# 7draft_onBoard.net
KiCad netlist of a schematic drawn in EAGLE
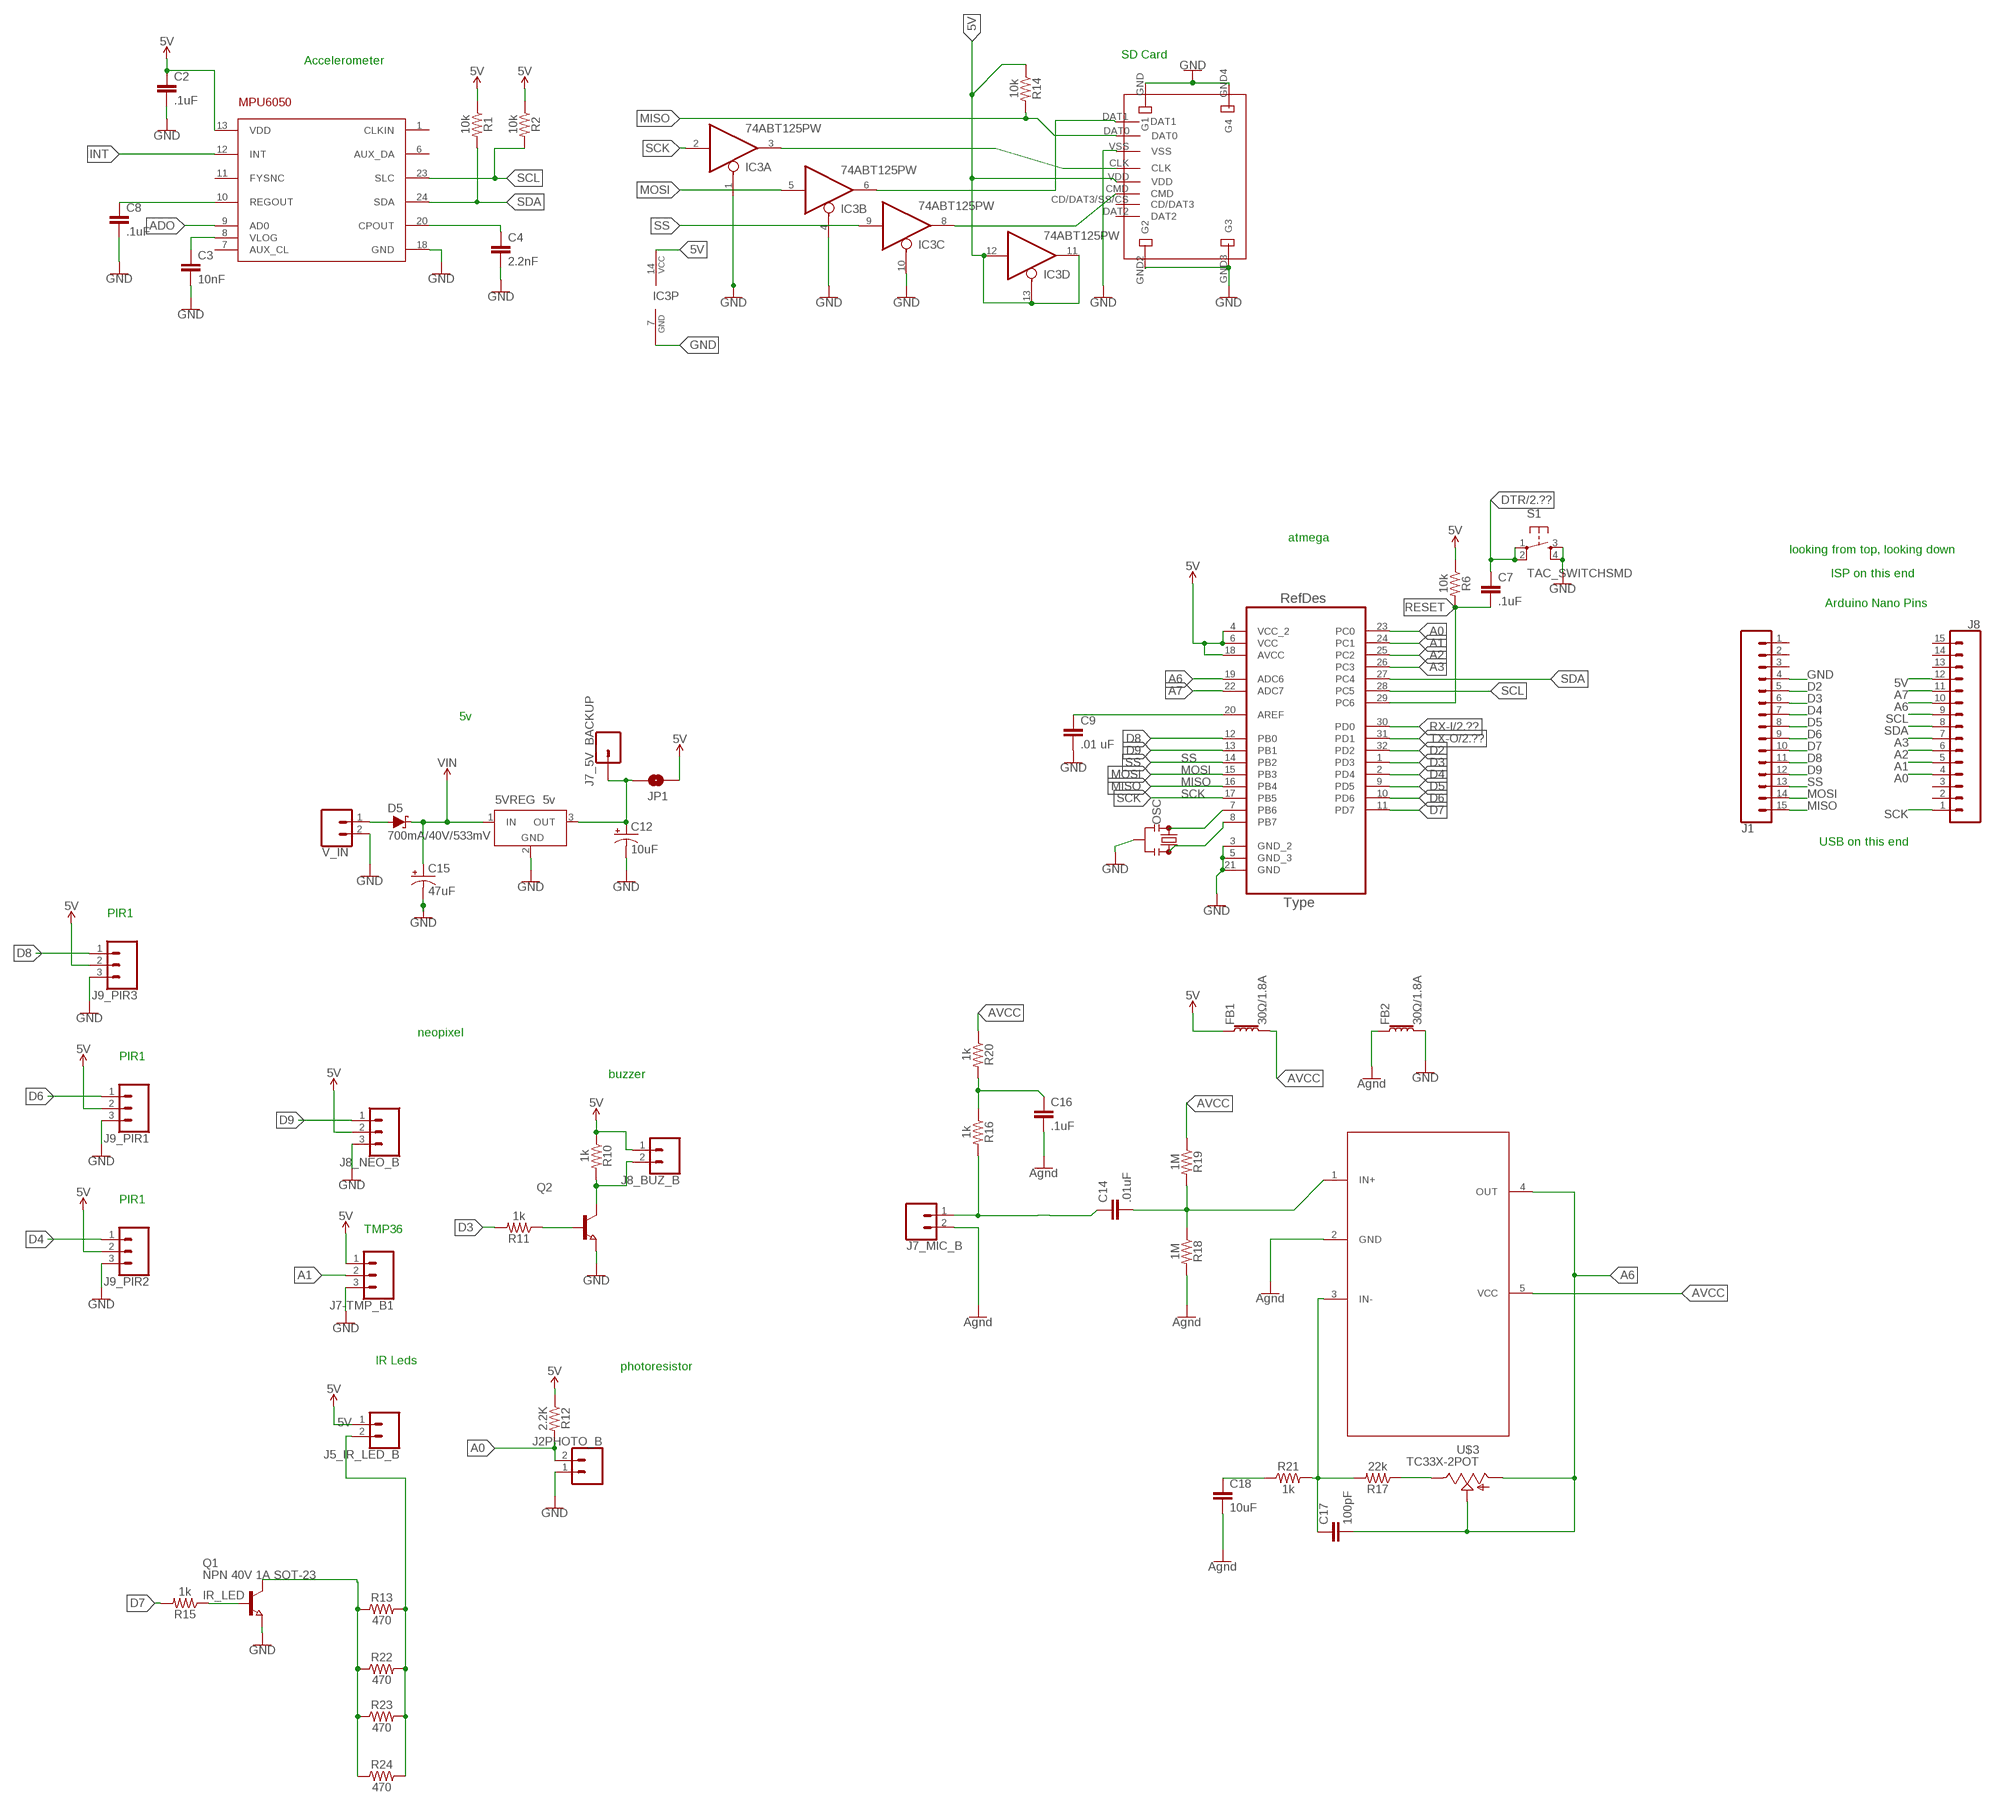
[diagram p0: schematic, sheet 1]
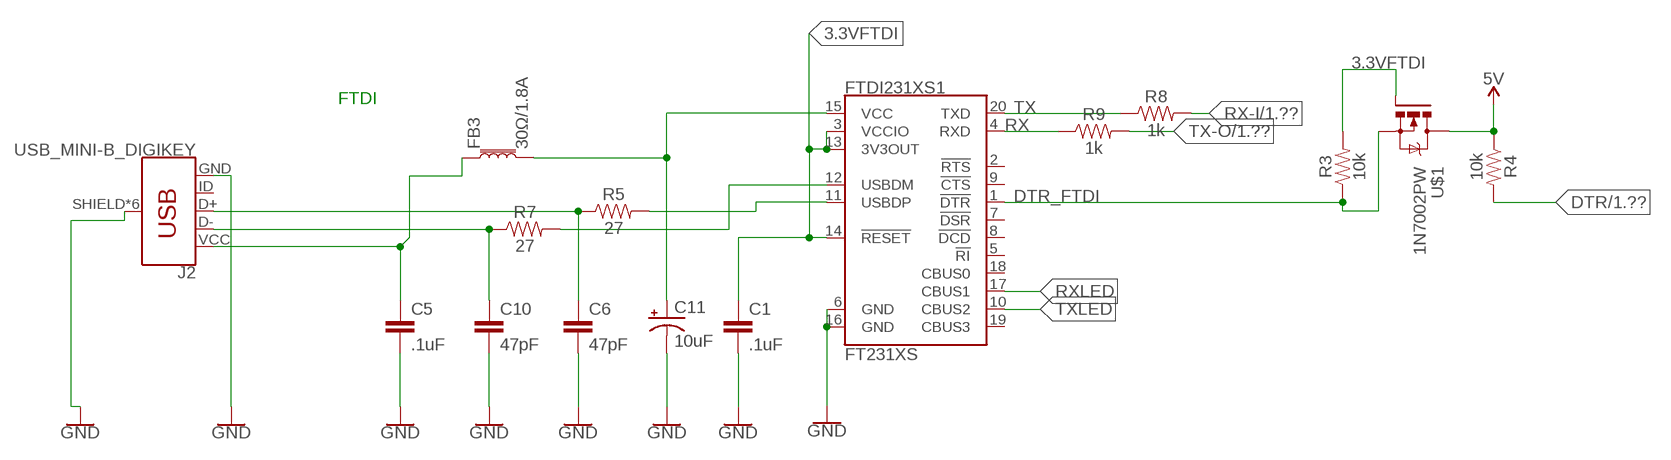
[diagram p1: schematic, sheet 2]

(export (version "E")
  (design (tool "Eeschema 10.0.6"))
  (components
    (comp (ref "C1")
      (value ".1uF")
      (footprint "eagle-import:0402-CAP")
      (libsource (lib "eagle-import") (part ".22UF-CER"))
    )
    (comp (ref "C5")
      (value ".1uF")
      (footprint "eagle-import:0402-CAP")
      (libsource (lib "eagle-import") (part ".22UF-CER"))
    )
    (comp (ref "C6")
      (value "47pF")
      (footprint "eagle-import:0402-CAP")
      (libsource (lib "eagle-import") (part ".22UF-CER"))
    )
    (comp (ref "C10")
      (value "47pF")
      (footprint "eagle-import:0402-CAP")
      (libsource (lib "eagle-import") (part ".22UF-CER"))
    )
    (comp (ref "C11")
      (value "10uF")
      (footprint "eagle-import:EIA3216")
      (libsource (lib "eagle-import") (part "10UF-TANT"))
    )
    (comp (ref "FB3")
      (value "30Ω/1.8A")
      (footprint "eagle-import:0603")
      (libsource (lib "eagle-import") (part "FERRITE_BEAD-0603"))
    )
    (comp (ref "FTDI231XS1")
      (value "FT231XS")
      (footprint "eagle-import:SSOP20_L")
      (libsource (lib "eagle-import") (part "FT231XS"))
    )
    (comp (ref "J2")
      (value "USB_MINI-B_DIGIKEY")
      (footprint "eagle-import:MICRO-USB-DIGIKEY-FCI2")
      (libsource (lib "eagle-import") (part "USB_MINI-B_DIGIKEY"))
    )
    (comp (ref "R3")
      (value "10k")
      (footprint "eagle-import:0603")
      (libsource (lib "eagle-import") (part "0.05OHM-0603-1/5W-1%"))
    )
    (comp (ref "R4")
      (value "10k")
      (footprint "eagle-import:0603")
      (libsource (lib "eagle-import") (part "0.05OHM-0603-1/5W-1%"))
    )
    (comp (ref "R5")
      (value "27")
      (footprint "eagle-import:0603")
      (libsource (lib "eagle-import") (part "0.05OHM-0603-1/5W-1%"))
    )
    (comp (ref "R7")
      (value "27")
      (footprint "eagle-import:0603")
      (libsource (lib "eagle-import") (part "0.05OHM-0603-1/5W-1%"))
    )
    (comp (ref "R8")
      (value "1k")
      (footprint "eagle-import:0603")
      (libsource (lib "eagle-import") (part "0.05OHM-0603-1/5W-1%"))
    )
    (comp (ref "R9")
      (value "1k")
      (footprint "eagle-import:0603")
      (libsource (lib "eagle-import") (part "0.05OHM-0603-1/5W-1%"))
    )
    (comp (ref "U$1")
      (value "1N7002PW")
      (footprint "eagle-import:SOT323W_INFINEON")
      (libsource (lib "eagle-import") (part "1N7002PW"))
    )
    (comp (ref "5VREG")
      (value "5v")
      (footprint "eagle-import:SOT223")
      (fields (field (name "MPN") "LT1129CST-5#PBF"))
      (libsource (lib "eagle-import") (part "LT1129CST5"))
    )
    (comp (ref "ATMEGA328P-AU")
      (value "ATMEGA328P-AU")
      (footprint "eagle-import:QFP80P900X900X120-32N")
      (libsource (lib "eagle-import") (part "ATMEGA328P-AU"))
    )
    (comp (ref "C2")
      (value ".1uF")
      (footprint "eagle-import:0402-CAP")
      (libsource (lib "eagle-import") (part ".22UF-CER"))
    )
    (comp (ref "C3")
      (value "10nF")
      (footprint "eagle-import:0402-CAP")
      (libsource (lib "eagle-import") (part ".22UF-CER"))
    )
    (comp (ref "C4")
      (value "2.2nF")
      (footprint "eagle-import:0402-CAP")
      (libsource (lib "eagle-import") (part ".22UF-CER"))
    )
    (comp (ref "C7")
      (value ".1uF")
      (footprint "eagle-import:0402-CAP")
      (libsource (lib "eagle-import") (part ".22UF-CER"))
    )
    (comp (ref "C8")
      (value ".1uF")
      (footprint "eagle-import:0402-CAP")
      (libsource (lib "eagle-import") (part ".22UF-CER"))
    )
    (comp (ref "C9")
      (value ".01 uF")
      (footprint "eagle-import:0402-CAP")
      (libsource (lib "eagle-import") (part ".22UF-CER"))
    )
    (comp (ref "C12")
      (value "10uF")
      (footprint "eagle-import:EIA3216")
      (libsource (lib "eagle-import") (part "10UF-TANT"))
    )
    (comp (ref "C14")
      (value ".01uF")
      (footprint "eagle-import:0402-CAP")
      (libsource (lib "eagle-import") (part ".22UF-CER"))
    )
    (comp (ref "C15")
      (value "47uF")
      (footprint "eagle-import:EIA3216")
      (libsource (lib "eagle-import") (part "10UF-TANT"))
    )
    (comp (ref "C16")
      (value ".1uF")
      (footprint "eagle-import:0402-CAP")
      (libsource (lib "eagle-import") (part ".22UF-CER"))
    )
    (comp (ref "C17")
      (value "100pF")
      (footprint "eagle-import:0402-CAP")
      (libsource (lib "eagle-import") (part ".22UF-CER"))
    )
    (comp (ref "C18")
      (value "10uF")
      (footprint "eagle-import:0402-CAP")
      (libsource (lib "eagle-import") (part ".22UF-CER"))
    )
    (comp (ref "D5")
      (value "700mA/40V/533mV")
      (footprint "eagle-import:SOT23-3")
      (libsource (lib "eagle-import") (part "DIODE-SCHOTTKY-ZLLS500"))
    )
    (comp (ref "FB1")
      (value "30Ω/1.8A")
      (footprint "eagle-import:0603")
      (libsource (lib "eagle-import") (part "FERRITE_BEAD-0603"))
    )
    (comp (ref "FB2")
      (value "30Ω/1.8A")
      (footprint "eagle-import:0603")
      (libsource (lib "eagle-import") (part "FERRITE_BEAD-0603"))
    )
    (comp (ref "IC3")
      (value "74ABT125PW")
      (footprint "eagle-import:TSSOP14")
      (libsource (lib "eagle-import") (part "74125PWABT"))
    )
    (comp (ref "IC4")
      (value "MAX4466KS")
      (footprint "eagle-import:SC70-5")
      (libsource (lib "eagle-import") (part "MAX4466KS"))
    )
    (comp (ref "J1")
      (value "CONN_15")
      (footprint "eagle-import:1X15")
      (libsource (lib "eagle-import") (part "CONN_15"))
    )
    (comp (ref "J2PHOTO_B")
      (value "CONN_02LOCK")
      (footprint "eagle-import:1X02_LOCK")
      (libsource (lib "eagle-import") (part "CONN_02LOCK"))
    )
    (comp (ref "J5_IR_LED_B")
      (value "CONN_02LOCK")
      (footprint "eagle-import:1X02_LOCK")
      (libsource (lib "eagle-import") (part "CONN_02LOCK"))
    )
    (comp (ref "J7-TMP_B1")
      (value "CONN_03")
      (footprint "eagle-import:1X03")
      (libsource (lib "eagle-import") (part "CONN_03"))
    )
    (comp (ref "J7_5V_BACKUP")
      (value "CONN_01")
      (footprint "eagle-import:1X01")
      (libsource (lib "eagle-import") (part "CONN_01"))
    )
    (comp (ref "J7_MIC_B")
      (value "CONN_02LOCK")
      (footprint "eagle-import:1X02_LOCK")
      (libsource (lib "eagle-import") (part "CONN_02LOCK"))
    )
    (comp (ref "J8")
      (value "CONN_15")
      (footprint "eagle-import:1X15")
      (libsource (lib "eagle-import") (part "CONN_15"))
    )
    (comp (ref "J8_BUZ_B")
      (value "CONN_02LOCK")
      (footprint "eagle-import:1X02_LOCK")
      (libsource (lib "eagle-import") (part "CONN_02LOCK"))
    )
    (comp (ref "J8_NEO_B")
      (value "CONN_03")
      (footprint "eagle-import:1X03")
      (libsource (lib "eagle-import") (part "CONN_03"))
    )
    (comp (ref "J9_PIR1")
      (value "CONN_03")
      (footprint "eagle-import:1X03")
      (libsource (lib "eagle-import") (part "CONN_03"))
    )
    (comp (ref "J9_PIR2")
      (value "CONN_03")
      (footprint "eagle-import:1X03")
      (libsource (lib "eagle-import") (part "CONN_03"))
    )
    (comp (ref "J9_PIR3")
      (value "CONN_03")
      (footprint "eagle-import:1X03")
      (libsource (lib "eagle-import") (part "CONN_03"))
    )
    (comp (ref "JP1")
      (value "JUMPER-SMT_2_NO_NO-SILK_ROUND")
      (footprint "eagle-import:SMT-JUMPER_2_NO_NO-SILK_ROUND")
      (libsource (lib "eagle-import") (part "JUMPER-SMT_2_NO_NO-SILK_ROUND"))
    )
    (comp (ref "MPU6050")
      (value "MPU-6050")
      (footprint "eagle-import:QFN24-4X4")
      (libsource (lib "eagle-import") (part "MPU-6050"))
    )
    (comp (ref "OSC")
      (value "RESONATORSMD-3.2X1.3")
      (footprint "eagle-import:RESONATOR-SMD-3.2X1.3")
      (libsource (lib "eagle-import") (part "RESONATORSMD-3.2X1.3"))
    )
    (comp (ref "Q1")
      (value "NPN 40V 1A SOT-23")
      (footprint "eagle-import:SOT23")
      (libsource (lib "eagle-import") (part "NPN-TRANSISTOR_SOT23"))
    )
    (comp (ref "Q2")
      (value "NPN-TRANSISTOR_SOT23")
      (footprint "eagle-import:SOT23")
      (libsource (lib "eagle-import") (part "NPN-TRANSISTOR_SOT23"))
    )
    (comp (ref "R1")
      (value "10k")
      (footprint "eagle-import:0603")
      (libsource (lib "eagle-import") (part "0.05OHM-0603-1/5W-1%"))
    )
    (comp (ref "R2")
      (value "10k")
      (footprint "eagle-import:0603")
      (libsource (lib "eagle-import") (part "0.05OHM-0603-1/5W-1%"))
    )
    (comp (ref "R6")
      (value "10k")
      (footprint "eagle-import:0603")
      (libsource (lib "eagle-import") (part "0.05OHM-0603-1/5W-1%"))
    )
    (comp (ref "R10")
      (value "1k")
      (footprint "eagle-import:0603")
      (libsource (lib "eagle-import") (part "0.05OHM-0603-1/5W-1%"))
    )
    (comp (ref "R11")
      (value "1k")
      (footprint "eagle-import:0603")
      (libsource (lib "eagle-import") (part "0.05OHM-0603-1/5W-1%"))
    )
    (comp (ref "R12")
      (value "2.2K")
      (footprint "eagle-import:0603")
      (libsource (lib "eagle-import") (part "0.05OHM-0603-1/5W-1%"))
    )
    (comp (ref "R13")
      (value "470")
      (footprint "eagle-import:0603")
      (libsource (lib "eagle-import") (part "2.2MOHM-1/10W-5%(0603)"))
    )
    (comp (ref "R14")
      (value "10k")
      (footprint "eagle-import:0603")
      (libsource (lib "eagle-import") (part "0.05OHM-0603-1/5W-1%"))
    )
    (comp (ref "R15")
      (value "1k")
      (footprint "eagle-import:0603")
      (libsource (lib "eagle-import") (part "0.05OHM-0603-1/5W-1%"))
    )
    (comp (ref "R16")
      (value "1k")
      (footprint "eagle-import:0603")
      (libsource (lib "eagle-import") (part "0.05OHM-0603-1/5W-1%"))
    )
    (comp (ref "R17")
      (value "22k")
      (footprint "eagle-import:0603")
      (libsource (lib "eagle-import") (part "0.05OHM-0603-1/5W-1%"))
    )
    (comp (ref "R18")
      (value "1M")
      (footprint "eagle-import:0603")
      (libsource (lib "eagle-import") (part "0.05OHM-0603-1/5W-1%"))
    )
    (comp (ref "R19")
      (value "1M")
      (footprint "eagle-import:0603")
      (libsource (lib "eagle-import") (part "0.05OHM-0603-1/5W-1%"))
    )
    (comp (ref "R20")
      (value "1k")
      (footprint "eagle-import:0603")
      (libsource (lib "eagle-import") (part "0.05OHM-0603-1/5W-1%"))
    )
    (comp (ref "R21")
      (value "1k")
      (footprint "eagle-import:0603")
      (libsource (lib "eagle-import") (part "0.05OHM-0603-1/5W-1%"))
    )
    (comp (ref "R22")
      (value "470")
      (footprint "eagle-import:0603")
      (libsource (lib "eagle-import") (part "2.2MOHM-1/10W-5%(0603)"))
    )
    (comp (ref "R23")
      (value "470")
      (footprint "eagle-import:0603")
      (libsource (lib "eagle-import") (part "2.2MOHM-1/10W-5%(0603)"))
    )
    (comp (ref "R24")
      (value "470")
      (footprint "eagle-import:0603")
      (libsource (lib "eagle-import") (part "2.2MOHM-1/10W-5%(0603)"))
    )
    (comp (ref "S1")
      (value "TAC_SWITCHSMD")
      (footprint "eagle-import:TACTILE-SWITCH-SMD")
      (libsource (lib "eagle-import") (part "TAC_SWITCHSMD"))
    )
    (comp (ref "U$2")
      (value "WM6698TR-ND_MICROSD")
      (footprint "eagle-import:MICROSD2")
      (libsource (lib "eagle-import") (part "WM6698TR-ND_MICROSD"))
    )
    (comp (ref "U$3")
      (value "TC33X-2POT")
      (footprint "eagle-import:TC33X-2")
      (libsource (lib "eagle-import") (part "TC33X-2POT"))
    )
    (comp (ref "V_IN")
      (value "CONN_02LOCK")
      (footprint "eagle-import:1X02_LOCK")
      (libsource (lib "eagle-import") (part "CONN_02LOCK"))
    )
  )
  (nets
    (net (code "1") (name "3.3VFTDI") (class "Default")
      (node (ref "C1") (pin "1") (pinfunction "1_1") (pintype "passive"))
      (node (ref "FTDI231XS1") (pin "13") (pinfunction "3V3OUT_13") (pintype "bidirectional"))
      (node (ref "FTDI231XS1") (pin "14") (pinfunction "~{RESET}_14") (pintype "bidirectional"))
      (node (ref "FTDI231XS1") (pin "3") (pinfunction "VCCIO_3") (pintype "bidirectional"))
      (node (ref "R3") (pin "2") (pinfunction "2_2") (pintype "passive"))
      (node (ref "U$1") (pin "1") (pinfunction "G_1") (pintype "passive"))
    )
    (net (code "2") (name "5V") (class "Default")
      (node (ref "ATMEGA328P-AU") (pin "18") (pinfunction "AVCC_18") (pintype "power_in"))
      (node (ref "ATMEGA328P-AU") (pin "4") (pinfunction "VCC_2_4") (pintype "power_in"))
      (node (ref "ATMEGA328P-AU") (pin "6") (pinfunction "VCC_6") (pintype "power_in"))
      (node (ref "C2") (pin "1") (pinfunction "1_1") (pintype "passive"))
      (node (ref "FB1") (pin "1") (pinfunction "1_1") (pintype "passive"))
      (node (ref "IC3") (pin "11") (pinfunction "O_11") (pintype "tri_state"))
      (node (ref "IC3") (pin "12") (pinfunction "I_12") (pintype "input"))
      (node (ref "IC3") (pin "13") (pinfunction "OE_13") (pintype "input"))
      (node (ref "IC3") (pin "14") (pinfunction "VCC_14") (pintype "power_in"))
      (node (ref "J5_IR_LED_B") (pin "1") (pinfunction "1_1") (pintype "passive"))
      (node (ref "J7-TMP_B1") (pin "1") (pinfunction "1_1") (pintype "passive"))
      (node (ref "J8") (pin "12") (pinfunction "12_12") (pintype "passive"))
      (node (ref "J8_BUZ_B") (pin "1") (pinfunction "1_1") (pintype "passive"))
      (node (ref "J8_NEO_B") (pin "2") (pinfunction "2_2") (pintype "passive"))
      (node (ref "J9_PIR1") (pin "2") (pinfunction "2_2") (pintype "passive"))
      (node (ref "J9_PIR2") (pin "2") (pinfunction "2_2") (pintype "passive"))
      (node (ref "J9_PIR3") (pin "2") (pinfunction "2_2") (pintype "passive"))
      (node (ref "JP1") (pin "1") (pinfunction "1_1") (pintype "passive"))
      (node (ref "MPU6050") (pin "13") (pinfunction "VDD_13") (pintype "bidirectional"))
      (node (ref "R1") (pin "1") (pinfunction "1_1") (pintype "passive"))
      (node (ref "R10") (pin "1") (pinfunction "1_1") (pintype "passive"))
      (node (ref "R12") (pin "1") (pinfunction "1_1") (pintype "passive"))
      (node (ref "R14") (pin "1") (pinfunction "1_1") (pintype "passive"))
      (node (ref "R2") (pin "1") (pinfunction "1_1") (pintype "passive"))
      (node (ref "R4") (pin "1") (pinfunction "1_1") (pintype "passive"))
      (node (ref "R6") (pin "1") (pinfunction "1_1") (pintype "passive"))
      (node (ref "U$1") (pin "3") (pinfunction "D_3") (pintype "passive"))
      (node (ref "U$2") (pin "VDD") (pinfunction "VDD_VDD") (pintype "bidirectional"))
    )
    (net (code "3") (name "A0") (class "Default")
      (node (ref "ATMEGA328P-AU") (pin "23") (pinfunction "PC0_23") (pintype "bidirectional"))
      (node (ref "J2PHOTO_B") (pin "2") (pinfunction "2_2") (pintype "passive"))
      (node (ref "J8") (pin "4") (pinfunction "4_4") (pintype "passive"))
      (node (ref "R12") (pin "2") (pinfunction "2_2") (pintype "passive"))
    )
    (net (code "4") (name "A1") (class "Default")
      (node (ref "ATMEGA328P-AU") (pin "24") (pinfunction "PC1_24") (pintype "bidirectional"))
      (node (ref "J7-TMP_B1") (pin "2") (pinfunction "2_2") (pintype "passive"))
      (node (ref "J8") (pin "5") (pinfunction "5_5") (pintype "passive"))
    )
    (net (code "5") (name "A2") (class "Default")
      (node (ref "ATMEGA328P-AU") (pin "25") (pinfunction "PC2_25") (pintype "bidirectional"))
      (node (ref "J8") (pin "6") (pinfunction "6_6") (pintype "passive"))
    )
    (net (code "6") (name "A3") (class "Default")
      (node (ref "ATMEGA328P-AU") (pin "26") (pinfunction "PC3_26") (pintype "bidirectional"))
      (node (ref "J8") (pin "7") (pinfunction "7_7") (pintype "passive"))
    )
    (net (code "7") (name "A6") (class "Default")
      (node (ref "ATMEGA328P-AU") (pin "19") (pinfunction "ADC6_19") (pintype "input"))
      (node (ref "C17") (pin "2") (pinfunction "2_2") (pintype "passive"))
      (node (ref "IC4") (pin "4") (pinfunction "OUT_4") (pintype "bidirectional"))
      (node (ref "J8") (pin "10") (pinfunction "10_10") (pintype "passive"))
      (node (ref "U$3") (pin "2") (pinfunction "2_2") (pintype "passive"))
      (node (ref "U$3") (pin "3") (pinfunction "3_3") (pintype "passive"))
    )
    (net (code "8") (name "A7") (class "Default")
      (node (ref "ATMEGA328P-AU") (pin "22") (pinfunction "ADC7_22") (pintype "input"))
      (node (ref "J8") (pin "11") (pinfunction "11_11") (pintype "passive"))
    )
    (net (code "9") (name "ADO") (class "Default")
      (node (ref "MPU6050") (pin "9") (pinfunction "AD0_9") (pintype "bidirectional"))
    )
    (net (code "10") (name "AVCC") (class "Default")
      (node (ref "FB1") (pin "2") (pinfunction "2_2") (pintype "passive"))
      (node (ref "IC4") (pin "5") (pinfunction "VCC_5") (pintype "bidirectional"))
      (node (ref "R19") (pin "1") (pinfunction "1_1") (pintype "passive"))
      (node (ref "R20") (pin "1") (pinfunction "1_1") (pintype "passive"))
    )
    (net (code "11") (name "D2") (class "Default")
      (node (ref "ATMEGA328P-AU") (pin "32") (pinfunction "PD2_32") (pintype "bidirectional"))
      (node (ref "J1") (pin "5") (pinfunction "5_5") (pintype "passive"))
    )
    (net (code "12") (name "D3") (class "Default")
      (node (ref "ATMEGA328P-AU") (pin "1") (pinfunction "PD3_1") (pintype "bidirectional"))
      (node (ref "J1") (pin "6") (pinfunction "6_6") (pintype "passive"))
      (node (ref "R11") (pin "2") (pinfunction "2_2") (pintype "passive"))
    )
    (net (code "13") (name "D4") (class "Default")
      (node (ref "ATMEGA328P-AU") (pin "2") (pinfunction "PD4_2") (pintype "bidirectional"))
      (node (ref "J1") (pin "7") (pinfunction "7_7") (pintype "passive"))
      (node (ref "J9_PIR2") (pin "1") (pinfunction "1_1") (pintype "passive"))
    )
    (net (code "14") (name "D5") (class "Default")
      (node (ref "ATMEGA328P-AU") (pin "9") (pinfunction "PD5_9") (pintype "bidirectional"))
      (node (ref "J1") (pin "8") (pinfunction "8_8") (pintype "passive"))
    )
    (net (code "15") (name "D6") (class "Default")
      (node (ref "ATMEGA328P-AU") (pin "10") (pinfunction "PD6_10") (pintype "bidirectional"))
      (node (ref "J1") (pin "9") (pinfunction "9_9") (pintype "passive"))
      (node (ref "J9_PIR1") (pin "1") (pinfunction "1_1") (pintype "passive"))
    )
    (net (code "16") (name "D7") (class "Default")
      (node (ref "ATMEGA328P-AU") (pin "11") (pinfunction "PD7_11") (pintype "bidirectional"))
      (node (ref "J1") (pin "10") (pinfunction "10_10") (pintype "passive"))
      (node (ref "R15") (pin "2") (pinfunction "2_2") (pintype "passive"))
    )
    (net (code "17") (name "D8") (class "Default")
      (node (ref "ATMEGA328P-AU") (pin "12") (pinfunction "PB0_12") (pintype "bidirectional"))
      (node (ref "J1") (pin "11") (pinfunction "11_11") (pintype "passive"))
      (node (ref "J9_PIR3") (pin "1") (pinfunction "1_1") (pintype "passive"))
    )
    (net (code "18") (name "D9") (class "Default")
      (node (ref "ATMEGA328P-AU") (pin "13") (pinfunction "PB1_13") (pintype "bidirectional"))
      (node (ref "J1") (pin "12") (pinfunction "12_12") (pintype "passive"))
      (node (ref "J8_NEO_B") (pin "1") (pinfunction "1_1") (pintype "passive"))
    )
    (net (code "19") (name "DTR") (class "Default")
      (node (ref "C7") (pin "1") (pinfunction "1_1") (pintype "passive"))
      (node (ref "R4") (pin "2") (pinfunction "2_2") (pintype "passive"))
      (node (ref "S1") (pin "1") (pinfunction "1_1") (pintype "passive"))
      (node (ref "S1") (pin "2") (pinfunction "2_2") (pintype "passive"))
    )
    (net (code "20") (name "DTR_FTDI") (class "Default")
      (node (ref "FTDI231XS1") (pin "1") (pinfunction "~{DTR}_1") (pintype "bidirectional"))
      (node (ref "R3") (pin "1") (pinfunction "1_1") (pintype "passive"))
      (node (ref "U$1") (pin "2") (pinfunction "S_2") (pintype "passive"))
    )
    (net (code "21") (name "GND") (class "Default")
      (node (ref "5VREG") (pin "2") (pinfunction "GND_2") (pintype "power_in"))
      (node (ref "ATMEGA328P-AU") (pin "21") (pinfunction "GND_21") (pintype "passive"))
      (node (ref "ATMEGA328P-AU") (pin "3") (pinfunction "GND_2_3") (pintype "passive"))
      (node (ref "ATMEGA328P-AU") (pin "5") (pinfunction "GND_3_5") (pintype "passive"))
      (node (ref "C1") (pin "2") (pinfunction "2_2") (pintype "passive"))
      (node (ref "C10") (pin "2") (pinfunction "2_2") (pintype "passive"))
      (node (ref "C11") (pin "C") (pinfunction "-_C") (pintype "passive"))
      (node (ref "C12") (pin "C") (pinfunction "-_C") (pintype "passive"))
      (node (ref "C15") (pin "C") (pinfunction "-_C") (pintype "passive"))
      (node (ref "C16") (pin "2") (pinfunction "2_2") (pintype "passive"))
      (node (ref "C18") (pin "2") (pinfunction "2_2") (pintype "passive"))
      (node (ref "C2") (pin "2") (pinfunction "2_2") (pintype "passive"))
      (node (ref "C3") (pin "2") (pinfunction "2_2") (pintype "passive"))
      (node (ref "C4") (pin "2") (pinfunction "2_2") (pintype "passive"))
      (node (ref "C5") (pin "2") (pinfunction "2_2") (pintype "passive"))
      (node (ref "C6") (pin "2") (pinfunction "2_2") (pintype "passive"))
      (node (ref "C8") (pin "2") (pinfunction "2_2") (pintype "passive"))
      (node (ref "C9") (pin "2") (pinfunction "2_2") (pintype "passive"))
      (node (ref "FB2") (pin "1") (pinfunction "1_1") (pintype "passive"))
      (node (ref "FB2") (pin "2") (pinfunction "2_2") (pintype "passive"))
      (node (ref "FTDI231XS1") (pin "16") (pinfunction "GND_16") (pintype "bidirectional"))
      (node (ref "FTDI231XS1") (pin "6") (pinfunction "GND_6") (pintype "bidirectional"))
      (node (ref "IC3") (pin "1") (pinfunction "OE_1") (pintype "input"))
      (node (ref "IC3") (pin "10") (pinfunction "OE_10") (pintype "input"))
      (node (ref "IC3") (pin "4") (pinfunction "OE_4") (pintype "input"))
      (node (ref "IC3") (pin "7") (pinfunction "GND_7") (pintype "power_in"))
      (node (ref "IC4") (pin "2") (pinfunction "GND_2") (pintype "bidirectional"))
      (node (ref "J1") (pin "4") (pinfunction "4_4") (pintype "passive"))
      (node (ref "J2") (pin "GND") (pinfunction "GND_GND") (pintype "power_in"))
      (node (ref "J2") (pin "SHIELD") (pinfunction "SHIELD_SHIELD") (pintype "bidirectional"))
      (node (ref "J2") (pin "SHIELD1") (pinfunction "SHIELD_SHIELD1") (pintype "bidirectional"))
      (node (ref "J2") (pin "SHIELD2") (pinfunction "SHIELD_SHIELD2") (pintype "bidirectional"))
      (node (ref "J2") (pin "SHIELD3") (pinfunction "SHIELD_SHIELD3") (pintype "bidirectional"))
      (node (ref "J2") (pin "SHIELD4") (pinfunction "SHIELD_SHIELD4") (pintype "bidirectional"))
      (node (ref "J2") (pin "SHIELD5") (pinfunction "SHIELD_SHIELD5") (pintype "bidirectional"))
      (node (ref "J2PHOTO_B") (pin "1") (pinfunction "1_1") (pintype "passive"))
      (node (ref "J7-TMP_B1") (pin "3") (pinfunction "3_3") (pintype "passive"))
      (node (ref "J7_MIC_B") (pin "2") (pinfunction "2_2") (pintype "passive"))
      (node (ref "J8_NEO_B") (pin "3") (pinfunction "3_3") (pintype "passive"))
      (node (ref "J9_PIR1") (pin "3") (pinfunction "3_3") (pintype "passive"))
      (node (ref "J9_PIR2") (pin "3") (pinfunction "3_3") (pintype "passive"))
      (node (ref "J9_PIR3") (pin "3") (pinfunction "3_3") (pintype "passive"))
      (node (ref "MPU6050") (pin "18") (pinfunction "GND_18") (pintype "bidirectional"))
      (node (ref "OSC") (pin "2") (pinfunction "2_2") (pintype "passive"))
      (node (ref "Q1") (pin "2") (pinfunction "E_2") (pintype "passive"))
      (node (ref "Q2") (pin "2") (pinfunction "E_2") (pintype "passive"))
      (node (ref "R18") (pin "2") (pinfunction "2_2") (pintype "passive"))
      (node (ref "S1") (pin "3") (pinfunction "3_3") (pintype "passive"))
      (node (ref "S1") (pin "4") (pinfunction "4_4") (pintype "passive"))
      (node (ref "U$2") (pin "GND") (pinfunction "G1_GND") (pintype "bidirectional"))
      (node (ref "U$2") (pin "GND2") (pinfunction "G2_GND2") (pintype "bidirectional"))
      (node (ref "U$2") (pin "GND3") (pinfunction "G3_GND3") (pintype "bidirectional"))
      (node (ref "U$2") (pin "GND4") (pinfunction "G4_GND4") (pintype "bidirectional"))
      (node (ref "U$2") (pin "VSS") (pinfunction "VSS_VSS") (pintype "bidirectional"))
      (node (ref "V_IN") (pin "2") (pinfunction "2_2") (pintype "passive"))
    )
    (net (code "22") (name "INT") (class "Default")
      (node (ref "MPU6050") (pin "12") (pinfunction "INT_12") (pintype "bidirectional"))
    )
    (net (code "23") (name "IR_LED") (class "Default")
      (node (ref "Q1") (pin "1") (pinfunction "B_1") (pintype "passive"))
      (node (ref "R15") (pin "1") (pinfunction "1_1") (pintype "passive"))
    )
    (net (code "24") (name "MISO") (class "Default")
      (node (ref "ATMEGA328P-AU") (pin "16") (pinfunction "PB4_16") (pintype "bidirectional"))
      (node (ref "J1") (pin "15") (pinfunction "15_15") (pintype "passive"))
      (node (ref "R14") (pin "2") (pinfunction "2_2") (pintype "passive"))
      (node (ref "U$2") (pin "DAT0") (pinfunction "DAT0_DAT0") (pintype "bidirectional"))
    )
    (net (code "25") (name "MOSI") (class "Default")
      (node (ref "ATMEGA328P-AU") (pin "15") (pinfunction "PB3_15") (pintype "bidirectional"))
      (node (ref "IC3") (pin "5") (pinfunction "I_5") (pintype "input"))
      (node (ref "J1") (pin "14") (pinfunction "14_14") (pintype "passive"))
    )
    (net (code "26") (name "Net-(5VREGA-OUT)") (class "Default")
      (node (ref "5VREG") (pin "3") (pinfunction "OUT_3") (pintype "output"))
      (node (ref "C12") (pin "A") (pinfunction "+_A") (pintype "passive"))
      (node (ref "J7_5V_BACKUP") (pin "1") (pinfunction "1_1") (pintype "passive"))
      (node (ref "JP1") (pin "2") (pinfunction "2_2") (pintype "passive"))
    )
    (net (code "27") (name "Net-(ATMEGA328P-AU-AREF)") (class "Default")
      (node (ref "ATMEGA328P-AU") (pin "20") (pinfunction "AREF_20") (pintype "input"))
      (node (ref "C9") (pin "1") (pinfunction "1_1") (pintype "passive"))
    )
    (net (code "28") (name "Net-(ATMEGA328P-AU-PB6)") (class "Default")
      (node (ref "ATMEGA328P-AU") (pin "7") (pinfunction "PB6_7") (pintype "bidirectional"))
      (node (ref "OSC") (pin "1") (pinfunction "1_1") (pintype "passive"))
    )
    (net (code "29") (name "Net-(ATMEGA328P-AU-PB7)") (class "Default")
      (node (ref "ATMEGA328P-AU") (pin "8") (pinfunction "PB7_8") (pintype "bidirectional"))
      (node (ref "OSC") (pin "3") (pinfunction "3_3") (pintype "passive"))
    )
    (net (code "30") (name "Net-(C6-Pad1)") (class "Default")
      (node (ref "C6") (pin "1") (pinfunction "1_1") (pintype "passive"))
      (node (ref "J2") (pin "D+") (pinfunction "D+_D+") (pintype "bidirectional"))
      (node (ref "R5") (pin "1") (pinfunction "1_1") (pintype "passive"))
    )
    (net (code "31") (name "Net-(C10-Pad1)") (class "Default")
      (node (ref "C10") (pin "1") (pinfunction "1_1") (pintype "passive"))
      (node (ref "J2") (pin "D-") (pinfunction "D-_D-") (pintype "bidirectional"))
      (node (ref "R7") (pin "1") (pinfunction "1_1") (pintype "passive"))
    )
    (net (code "32") (name "Net-(C14-Pad1)") (class "Default")
      (node (ref "C14") (pin "1") (pinfunction "1_1") (pintype "passive"))
      (node (ref "J7_MIC_B") (pin "1") (pinfunction "1_1") (pintype "passive"))
      (node (ref "R16") (pin "2") (pinfunction "2_2") (pintype "passive"))
    )
    (net (code "33") (name "Net-(C16-Pad1)") (class "Default")
      (node (ref "C16") (pin "1") (pinfunction "1_1") (pintype "passive"))
      (node (ref "R16") (pin "1") (pinfunction "1_1") (pintype "passive"))
      (node (ref "R20") (pin "2") (pinfunction "2_2") (pintype "passive"))
    )
    (net (code "34") (name "Net-(C18-Pad1)") (class "Default")
      (node (ref "C18") (pin "1") (pinfunction "1_1") (pintype "passive"))
      (node (ref "R21") (pin "1") (pinfunction "1_1") (pintype "passive"))
    )
    (net (code "35") (name "Net-(D5-A)") (class "Default")
      (node (ref "D5") (pin "1") (pinfunction "A_1") (pintype "passive"))
      (node (ref "V_IN") (pin "1") (pinfunction "1_1") (pintype "passive"))
    )
    (net (code "36") (name "Net-(FTDI231XS1-USBDM)") (class "Default")
      (node (ref "FTDI231XS1") (pin "12") (pinfunction "USBDM_12") (pintype "bidirectional"))
      (node (ref "R7") (pin "2") (pinfunction "2_2") (pintype "passive"))
    )
    (net (code "37") (name "Net-(FTDI231XS1-USBDP)") (class "Default")
      (node (ref "FTDI231XS1") (pin "11") (pinfunction "USBDP_11") (pintype "bidirectional"))
      (node (ref "R5") (pin "2") (pinfunction "2_2") (pintype "passive"))
    )
    (net (code "38") (name "Net-(IC3A-O)") (class "Default")
      (node (ref "IC3") (pin "3") (pinfunction "O_3") (pintype "tri_state"))
      (node (ref "U$2") (pin "CLK") (pinfunction "CLK_CLK") (pintype "bidirectional"))
    )
    (net (code "39") (name "Net-(IC3B-O)") (class "Default")
      (node (ref "IC3") (pin "6") (pinfunction "O_6") (pintype "tri_state"))
      (node (ref "U$2") (pin "DAT1") (pinfunction "DAT1_DAT1") (pintype "bidirectional"))
    )
    (net (code "40") (name "Net-(IC3C-O)") (class "Default")
      (node (ref "IC3") (pin "8") (pinfunction "O_8") (pintype "tri_state"))
      (node (ref "U$2") (pin "CMD") (pinfunction "CMD_CMD") (pintype "bidirectional"))
    )
    (net (code "41") (name "Net-(IC4-IN+)") (class "Default")
      (node (ref "C14") (pin "2") (pinfunction "2_2") (pintype "passive"))
      (node (ref "IC4") (pin "1") (pinfunction "IN+_1") (pintype "bidirectional"))
      (node (ref "R18") (pin "1") (pinfunction "1_1") (pintype "passive"))
      (node (ref "R19") (pin "2") (pinfunction "2_2") (pintype "passive"))
    )
    (net (code "42") (name "Net-(IC4-IN-)") (class "Default")
      (node (ref "C17") (pin "1") (pinfunction "1_1") (pintype "passive"))
      (node (ref "IC4") (pin "3") (pinfunction "IN-_3") (pintype "bidirectional"))
      (node (ref "R17") (pin "2") (pinfunction "2_2") (pintype "passive"))
      (node (ref "R21") (pin "2") (pinfunction "2_2") (pintype "passive"))
    )
    (net (code "43") (name "Net-(J5_IR_LED_B-Pad2)") (class "Default")
      (node (ref "J5_IR_LED_B") (pin "2") (pinfunction "2_2") (pintype "passive"))
      (node (ref "R13") (pin "2") (pinfunction "2_2") (pintype "passive"))
      (node (ref "R22") (pin "2") (pinfunction "2_2") (pintype "passive"))
      (node (ref "R23") (pin "2") (pinfunction "2_2") (pintype "passive"))
      (node (ref "R24") (pin "2") (pinfunction "2_2") (pintype "passive"))
    )
    (net (code "44") (name "Net-(MPU6050-CPOUT)") (class "Default")
      (node (ref "C4") (pin "1") (pinfunction "1_1") (pintype "passive"))
      (node (ref "MPU6050") (pin "20") (pinfunction "CPOUT_20") (pintype "bidirectional"))
    )
    (net (code "45") (name "Net-(MPU6050-REGOUT)") (class "Default")
      (node (ref "C8") (pin "1") (pinfunction "1_1") (pintype "passive"))
      (node (ref "MPU6050") (pin "10") (pinfunction "REGOUT_10") (pintype "bidirectional"))
    )
    (net (code "46") (name "Net-(MPU6050-VLOG)") (class "Default")
      (node (ref "C3") (pin "1") (pinfunction "1_1") (pintype "passive"))
      (node (ref "MPU6050") (pin "8") (pinfunction "VLOG_8") (pintype "bidirectional"))
    )
    (net (code "47") (name "Net-(Q1-C)") (class "Default")
      (node (ref "Q1") (pin "3") (pinfunction "C_3") (pintype "passive"))
      (node (ref "R13") (pin "1") (pinfunction "1_1") (pintype "passive"))
      (node (ref "R22") (pin "1") (pinfunction "1_1") (pintype "passive"))
      (node (ref "R23") (pin "1") (pinfunction "1_1") (pintype "passive"))
      (node (ref "R24") (pin "1") (pinfunction "1_1") (pintype "passive"))
    )
    (net (code "48") (name "Net-(Q2-B)") (class "Default")
      (node (ref "Q2") (pin "1") (pinfunction "B_1") (pintype "passive"))
      (node (ref "R11") (pin "1") (pinfunction "1_1") (pintype "passive"))
    )
    (net (code "49") (name "Net-(Q2-C)") (class "Default")
      (node (ref "J8_BUZ_B") (pin "2") (pinfunction "2_2") (pintype "passive"))
      (node (ref "Q2") (pin "3") (pinfunction "C_3") (pintype "passive"))
      (node (ref "R10") (pin "2") (pinfunction "2_2") (pintype "passive"))
    )
    (net (code "50") (name "Net-(R17-Pad1)") (class "Default")
      (node (ref "R17") (pin "1") (pinfunction "1_1") (pintype "passive"))
      (node (ref "U$3") (pin "1") (pinfunction "1_1") (pintype "passive"))
    )
    (net (code "51") (name "RESET") (class "Default")
      (node (ref "ATMEGA328P-AU") (pin "29") (pinfunction "PC6_29") (pintype "bidirectional"))
      (node (ref "C7") (pin "2") (pinfunction "2_2") (pintype "passive"))
      (node (ref "R6") (pin "2") (pinfunction "2_2") (pintype "passive"))
    )
    (net (code "52") (name "RX") (class "Default")
      (node (ref "FTDI231XS1") (pin "4") (pinfunction "RXD_4") (pintype "bidirectional"))
      (node (ref "R9") (pin "1") (pinfunction "1_1") (pintype "passive"))
    )
    (net (code "53") (name "RX-I") (class "Default")
      (node (ref "ATMEGA328P-AU") (pin "30") (pinfunction "PD0_30") (pintype "bidirectional"))
      (node (ref "R8") (pin "2") (pinfunction "2_2") (pintype "passive"))
    )
    (net (code "54") (name "RXLED") (class "Default")
      (node (ref "FTDI231XS1") (pin "17") (pinfunction "CBUS1_17") (pintype "bidirectional"))
    )
    (net (code "55") (name "SCK") (class "Default")
      (node (ref "ATMEGA328P-AU") (pin "17") (pinfunction "PB5_17") (pintype "bidirectional"))
      (node (ref "IC3") (pin "2") (pinfunction "I_2") (pintype "input"))
      (node (ref "J8") (pin "1") (pinfunction "1_1") (pintype "passive"))
    )
    (net (code "56") (name "SCL") (class "Default")
      (node (ref "ATMEGA328P-AU") (pin "28") (pinfunction "PC5_28") (pintype "bidirectional"))
      (node (ref "J8") (pin "9") (pinfunction "9_9") (pintype "passive"))
      (node (ref "MPU6050") (pin "23") (pinfunction "SLC_23") (pintype "bidirectional"))
      (node (ref "R2") (pin "2") (pinfunction "2_2") (pintype "passive"))
    )
    (net (code "57") (name "SDA") (class "Default")
      (node (ref "ATMEGA328P-AU") (pin "27") (pinfunction "PC4_27") (pintype "bidirectional"))
      (node (ref "J8") (pin "8") (pinfunction "8_8") (pintype "passive"))
      (node (ref "MPU6050") (pin "24") (pinfunction "SDA_24") (pintype "bidirectional"))
      (node (ref "R1") (pin "2") (pinfunction "2_2") (pintype "passive"))
    )
    (net (code "58") (name "SS") (class "Default")
      (node (ref "ATMEGA328P-AU") (pin "14") (pinfunction "PB2_14") (pintype "bidirectional"))
      (node (ref "IC3") (pin "9") (pinfunction "I_9") (pintype "input"))
      (node (ref "J1") (pin "13") (pinfunction "13_13") (pintype "passive"))
    )
    (net (code "59") (name "TX") (class "Default")
      (node (ref "FTDI231XS1") (pin "20") (pinfunction "TXD_20") (pintype "bidirectional"))
      (node (ref "R8") (pin "1") (pinfunction "1_1") (pintype "passive"))
    )
    (net (code "60") (name "TX-O") (class "Default")
      (node (ref "ATMEGA328P-AU") (pin "31") (pinfunction "PD1_31") (pintype "bidirectional"))
      (node (ref "R9") (pin "2") (pinfunction "2_2") (pintype "passive"))
    )
    (net (code "61") (name "TXLED") (class "Default")
      (node (ref "FTDI231XS1") (pin "10") (pinfunction "CBUS2_10") (pintype "bidirectional"))
    )
    (net (code "62") (name "VIN") (class "Default")
      (node (ref "5VREG") (pin "1") (pinfunction "IN_1") (pintype "input"))
      (node (ref "C15") (pin "A") (pinfunction "+_A") (pintype "passive"))
      (node (ref "D5") (pin "3") (pinfunction "C_3") (pintype "passive"))
    )
    (net (code "63") (name "VUSB") (class "Default")
      (node (ref "C11") (pin "A") (pinfunction "+_A") (pintype "passive"))
      (node (ref "C5") (pin "1") (pinfunction "1_1") (pintype "passive"))
      (node (ref "FB3") (pin "1") (pinfunction "1_1") (pintype "passive"))
      (node (ref "FB3") (pin "2") (pinfunction "2_2") (pintype "passive"))
      (node (ref "FTDI231XS1") (pin "15") (pinfunction "VCC_15") (pintype "bidirectional"))
      (node (ref "J2") (pin "VCC") (pinfunction "VBUS_VCC") (pintype "power_in"))
    )
    (net (code "64") (name "unconnected-(FTDI231XS1-CBUS0-Pad18)") (class "Default")
      (node (ref "FTDI231XS1") (pin "18") (pinfunction "CBUS0_18") (pintype "bidirectional"))
    )
    (net (code "65") (name "unconnected-(FTDI231XS1-CBUS3-Pad19)") (class "Default")
      (node (ref "FTDI231XS1") (pin "19") (pinfunction "CBUS3_19") (pintype "bidirectional"))
    )
    (net (code "66") (name "unconnected-(FTDI231XS1-~{CTS}-Pad9)") (class "Default")
      (node (ref "FTDI231XS1") (pin "9") (pinfunction "~{CTS}_9") (pintype "bidirectional"))
    )
    (net (code "67") (name "unconnected-(FTDI231XS1-~{DCD}-Pad8)") (class "Default")
      (node (ref "FTDI231XS1") (pin "8") (pinfunction "~{DCD}_8") (pintype "bidirectional"))
    )
    (net (code "68") (name "unconnected-(FTDI231XS1-~{DSR}-Pad7)") (class "Default")
      (node (ref "FTDI231XS1") (pin "7") (pinfunction "~{DSR}_7") (pintype "bidirectional"))
    )
    (net (code "69") (name "unconnected-(FTDI231XS1-~{RI}-Pad5)") (class "Default")
      (node (ref "FTDI231XS1") (pin "5") (pinfunction "~{RI}_5") (pintype "bidirectional"))
    )
    (net (code "70") (name "unconnected-(FTDI231XS1-~{RTS}-Pad2)") (class "Default")
      (node (ref "FTDI231XS1") (pin "2") (pinfunction "~{RTS}_2") (pintype "bidirectional"))
    )
    (net (code "71") (name "unconnected-(J1-Pad1)") (class "Default")
      (node (ref "J1") (pin "1") (pinfunction "1_1") (pintype "passive"))
    )
    (net (code "72") (name "unconnected-(J1-Pad2)") (class "Default")
      (node (ref "J1") (pin "2") (pinfunction "2_2") (pintype "passive"))
    )
    (net (code "73") (name "unconnected-(J1-Pad3)") (class "Default")
      (node (ref "J1") (pin "3") (pinfunction "3_3") (pintype "passive"))
    )
    (net (code "74") (name "unconnected-(J2-PadID)") (class "Default")
      (node (ref "J2") (pin "ID") (pinfunction "ID_ID") (pintype "bidirectional"))
    )
    (net (code "75") (name "unconnected-(J8-Pad2)") (class "Default")
      (node (ref "J8") (pin "2") (pinfunction "2_2") (pintype "passive"))
    )
    (net (code "76") (name "unconnected-(J8-Pad3)") (class "Default")
      (node (ref "J8") (pin "3") (pinfunction "3_3") (pintype "passive"))
    )
    (net (code "77") (name "unconnected-(J8-Pad13)") (class "Default")
      (node (ref "J8") (pin "13") (pinfunction "13_13") (pintype "passive"))
    )
    (net (code "78") (name "unconnected-(J8-Pad14)") (class "Default")
      (node (ref "J8") (pin "14") (pinfunction "14_14") (pintype "passive"))
    )
    (net (code "79") (name "unconnected-(J8-Pad15)") (class "Default")
      (node (ref "J8") (pin "15") (pinfunction "15_15") (pintype "passive"))
    )
    (net (code "80") (name "unconnected-(MPU6050-AUX_CL-Pad7)") (class "Default")
      (node (ref "MPU6050") (pin "7") (pinfunction "AUX_CL_7") (pintype "bidirectional"))
    )
    (net (code "81") (name "unconnected-(MPU6050-AUX_DA-Pad6)") (class "Default")
      (node (ref "MPU6050") (pin "6") (pinfunction "AUX_DA_6") (pintype "bidirectional"))
    )
    (net (code "82") (name "unconnected-(MPU6050-CLKIN-Pad1)") (class "Default")
      (node (ref "MPU6050") (pin "1") (pinfunction "CLKIN_1") (pintype "bidirectional"))
    )
    (net (code "83") (name "unconnected-(MPU6050-FYSNC-Pad11)") (class "Default")
      (node (ref "MPU6050") (pin "11") (pinfunction "FYSNC_11") (pintype "bidirectional"))
    )
    (net (code "84") (name "unconnected-(U$2-CD{slash}DAT3-PadCD{slash}DAT3{slash}SS{slash}CS)") (class "Default")
      (node (ref "U$2") (pin "CD/DAT3/SS/CS") (pinfunction "CD/DAT3_CD/DAT3/SS/CS") (pintype "bidirectional"))
    )
    (net (code "85") (name "unconnected-(U$2-PadDAT2)") (class "Default")
      (node (ref "U$2") (pin "DAT2") (pinfunction "DAT2_DAT2") (pintype "bidirectional"))
    )
  )
)
